# pico_tracker_v3_1.net
KiCad netlist of a schematic drawn in EAGLE
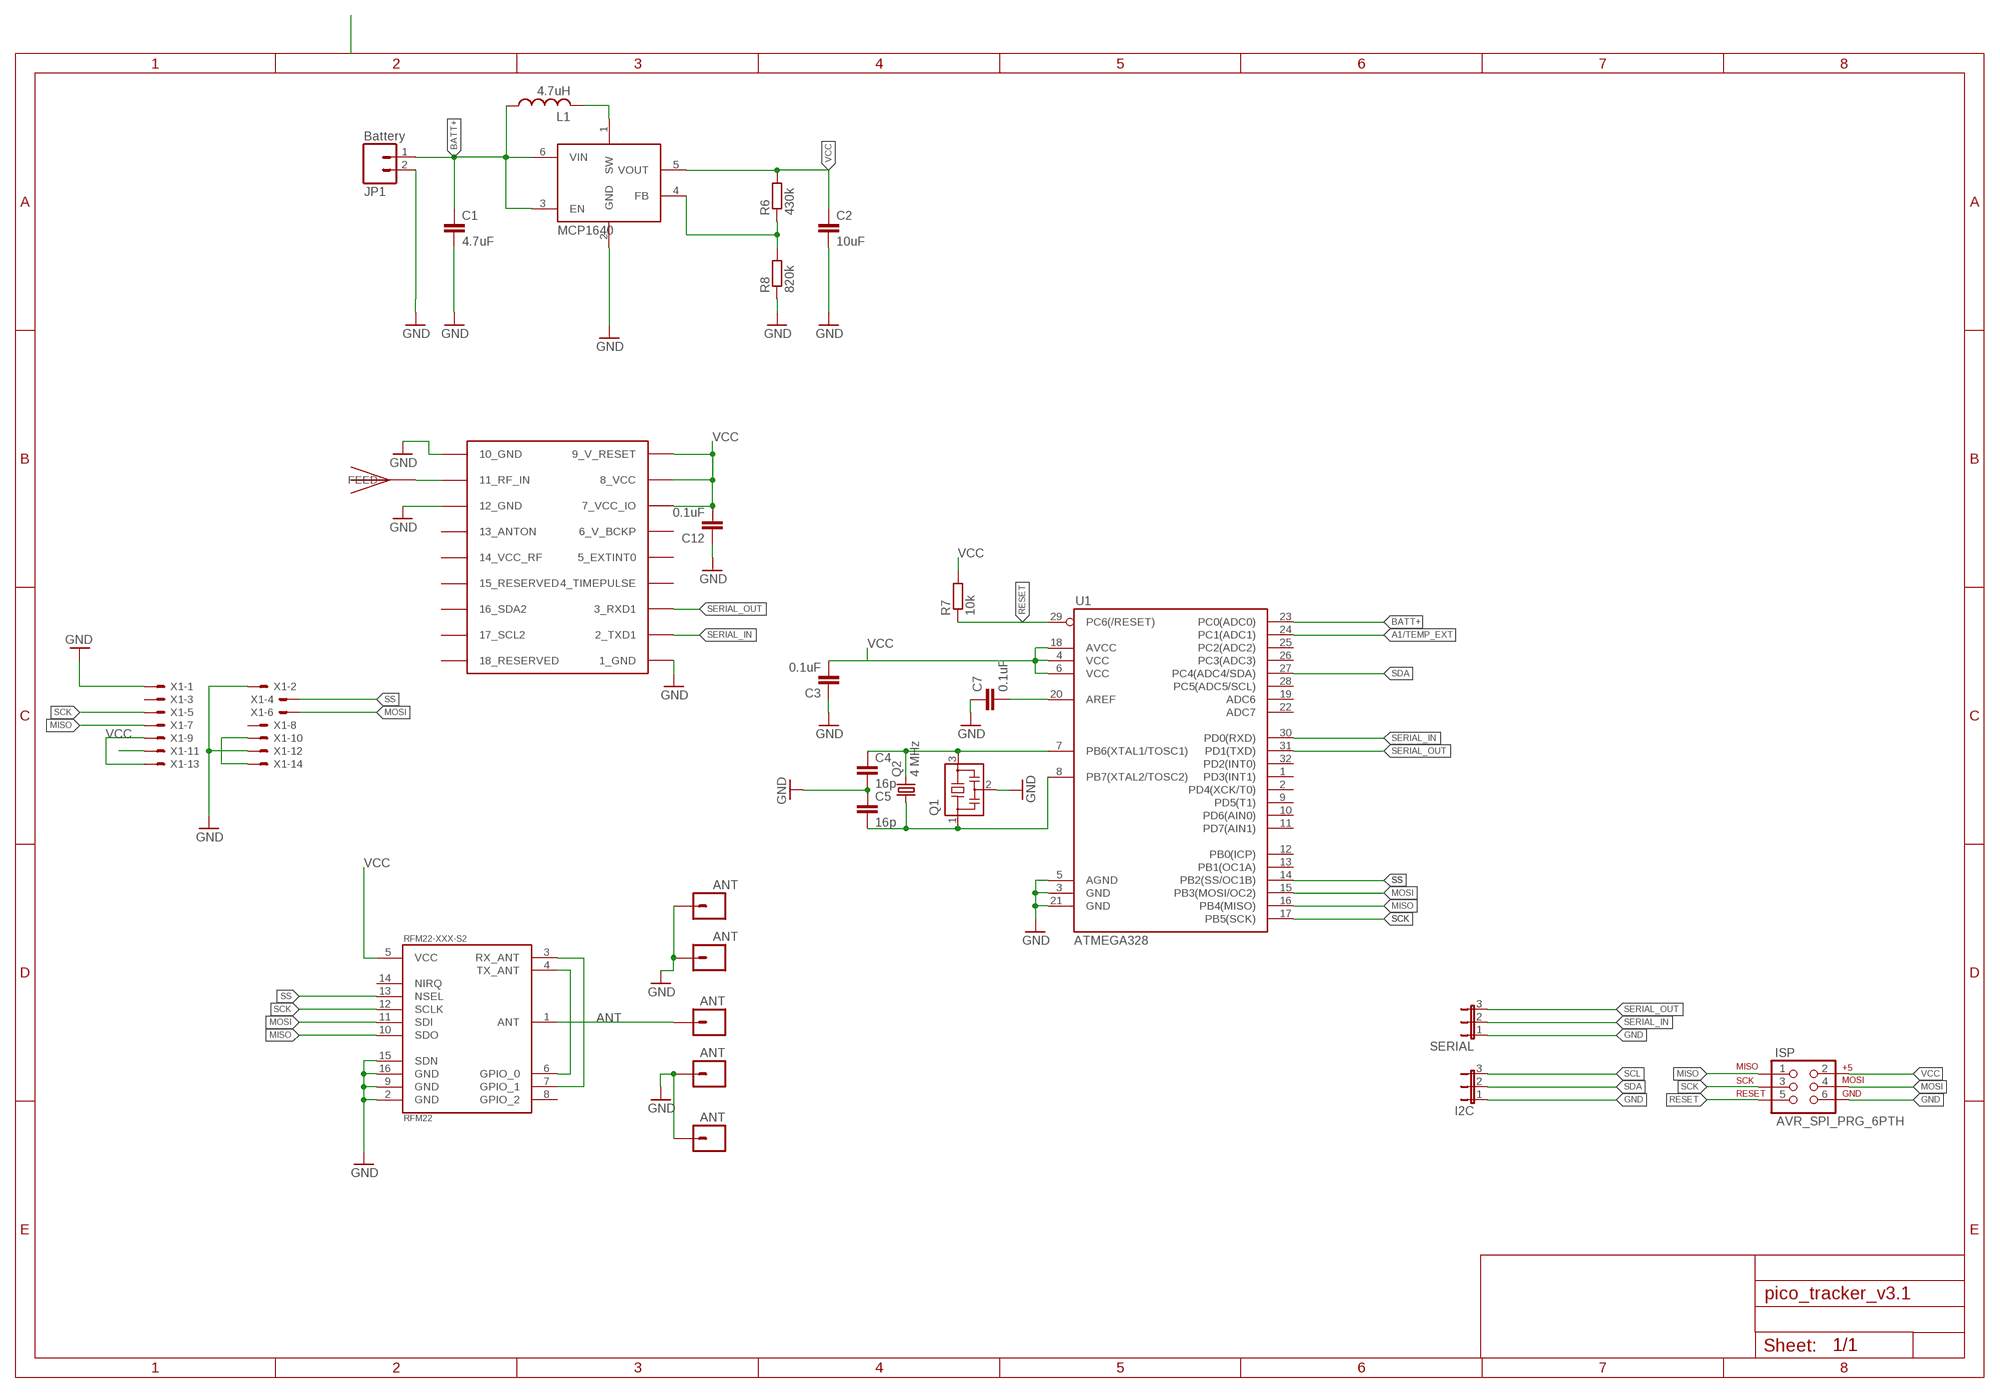
[diagram p0: schematic, sheet 1]

(export (version "E")
  (design (tool "Eeschema 10.0.6"))
  (components
    (comp (ref "C1")
      (value "4.7uF")
      (footprint "eagle-import:C0805")
      (libsource (lib "eagle-import") (part "C-EUC0805"))
    )
    (comp (ref "C2")
      (value "10uF")
      (footprint "eagle-import:C0805")
      (libsource (lib "eagle-import") (part "C-EUC0805"))
    )
    (comp (ref "C3")
      (value "0.1uF")
      (footprint "eagle-import:C0603")
      (libsource (lib "eagle-import") (part "C-EUC0603"))
    )
    (comp (ref "C4")
      (value "16p")
      (footprint "eagle-import:C0603")
      (libsource (lib "eagle-import") (part "C-EUC0603"))
    )
    (comp (ref "C5")
      (value "16p")
      (footprint "eagle-import:C0603")
      (libsource (lib "eagle-import") (part "C-EUC0603"))
    )
    (comp (ref "C7")
      (value "0.1uF")
      (footprint "eagle-import:C0603")
      (libsource (lib "eagle-import") (part "C-EUC0603"))
    )
    (comp (ref "C12")
      (value "0.1uF")
      (footprint "eagle-import:C0603")
      (libsource (lib "eagle-import") (part "C-EUC0603"))
    )
    (comp (ref "GND")
      (value "ANT")
      (footprint "eagle-import:1X01")
      (libsource (lib "eagle-import") (part "M01PTH"))
    )
    (comp (ref "GND17")
      (value "ANT")
      (footprint "eagle-import:1X01")
      (libsource (lib "eagle-import") (part "M01PTH"))
    )
    (comp (ref "GPS_ANT")
      (value "JTI_ANTENNA-1575AT43A40")
      (footprint "eagle-import:JTI_ANTENNA-1575AT43A40")
      (libsource (lib "eagle-import") (part "JTI_ANTENNA-1575AT43A40"))
    )
    (comp (ref "I2C")
      (value "JP2E")
      (footprint "eagle-import:JP2")
      (libsource (lib "eagle-import") (part "JP2E"))
    )
    (comp (ref "ISP")
      (value "AVR_SPI_PRG_6PTH")
      (footprint "eagle-import:2X3")
      (libsource (lib "eagle-import") (part "AVR_SPI_PRG_6PTH"))
    )
    (comp (ref "JP1")
      (value "Battery")
      (footprint "eagle-import:1X02")
      (libsource (lib "eagle-import") (part "M02PTH"))
    )
    (comp (ref "JP2")
      (value "ANT")
      (footprint "eagle-import:1X01")
      (libsource (lib "eagle-import") (part "M01PTH"))
    )
    (comp (ref "JP3")
      (value "ANT")
      (footprint "eagle-import:1X01")
      (libsource (lib "eagle-import") (part "M01PTH"))
    )
    (comp (ref "JP4")
      (value "ANT")
      (footprint "eagle-import:1X01")
      (libsource (lib "eagle-import") (part "M01PTH"))
    )
    (comp (ref "L1")
      (value "4.7uH")
      (footprint "eagle-import:LQH44")
      (libsource (lib "eagle-import") (part "LLQH44P_P0"))
    )
    (comp (ref "Q1")
      (value "CSTCR6M00G53Z")
      (footprint "eagle-import:CSTCR6M")
      (fields (field (name "MPN") "CSTCR6M00G53-R0"))
      (libsource (lib "eagle-import") (part "CSTCR6M00G53Z"))
    )
    (comp (ref "Q2")
      (value "4 MHz")
      (footprint "eagle-import:ABM03_HC49")
      (libsource (lib "eagle-import") (part "ABRACON_ABM3_CRYSTALABM03_HC49"))
    )
    (comp (ref "R6")
      (value "430k")
      (footprint "eagle-import:R0603")
      (libsource (lib "eagle-import") (part "R-EU_R0603"))
    )
    (comp (ref "R7")
      (value "10k")
      (footprint "eagle-import:R0603")
      (libsource (lib "eagle-import") (part "R-EU_R0603"))
    )
    (comp (ref "R8")
      (value "820k")
      (footprint "eagle-import:R0603")
      (libsource (lib "eagle-import") (part "R-EU_R0603"))
    )
    (comp (ref "RFM22-XXX-S2")
      (value "RFM22")
      (footprint "eagle-import:RFM22-XXX-S2")
      (libsource (lib "eagle-import") (part "RFM22"))
    )
    (comp (ref "SERIAL")
      (value "JP2E")
      (footprint "eagle-import:JP2")
      (libsource (lib "eagle-import") (part "JP2E"))
    )
    (comp (ref "U$3")
      (value "UBLOX_MAX-6")
      (footprint "eagle-import:UBLOX_MAX-6")
      (libsource (lib "eagle-import") (part "UBLOX_MAX-6"))
    )
    (comp (ref "U1")
      (value "ATMEGA328")
      (footprint "eagle-import:TQFP32-08")
      (libsource (lib "eagle-import") (part "ATMEGA168"))
    )
    (comp (ref "U2")
      (value "MCP1640")
      (footprint "eagle-import:SOT23-6")
      (libsource (lib "eagle-import") (part "MCP1640"))
    )
    (comp (ref "X1")
      (value "87758-1416")
      (footprint "eagle-import:87758-1416")
      (libsource (lib "eagle-import") (part "87758-1416"))
    )
  )
  (nets
    (net (code "1") (name "/ANT") (class "Default")
      (node (ref "JP2") (pin "1") (pinfunction "1_1") (pintype "passive"))
      (node (ref "RFM22-XXX-S2") (pin "1") (pinfunction "ANT_1") (pintype "bidirectional"))
    )
    (net (code "2") (name "A1{slash}TEMP_EXT") (class "Default")
      (node (ref "U1") (pin "24") (pinfunction "PC1(ADC1)_24") (pintype "bidirectional"))
    )
    (net (code "3") (name "BATT+") (class "Default")
      (node (ref "C1") (pin "1") (pinfunction "1_1") (pintype "passive"))
      (node (ref "JP1") (pin "1") (pinfunction "1_1") (pintype "passive"))
      (node (ref "L1") (pin "P$1") (pinfunction "1_P$1") (pintype "passive"))
      (node (ref "U1") (pin "23") (pinfunction "PC0(ADC0)_23") (pintype "bidirectional"))
      (node (ref "U2") (pin "3") (pinfunction "EN_3") (pintype "input"))
      (node (ref "U2") (pin "6") (pinfunction "VIN_6") (pintype "input"))
    )
    (net (code "4") (name "GND") (class "Default")
      (node (ref "C1") (pin "2") (pinfunction "2_2") (pintype "passive"))
      (node (ref "C12") (pin "1") (pinfunction "1_1") (pintype "passive"))
      (node (ref "C2") (pin "2") (pinfunction "2_2") (pintype "passive"))
      (node (ref "C3") (pin "1") (pinfunction "1_1") (pintype "passive"))
      (node (ref "C4") (pin "2") (pinfunction "2_2") (pintype "passive"))
      (node (ref "C5") (pin "1") (pinfunction "1_1") (pintype "passive"))
      (node (ref "C7") (pin "1") (pinfunction "1_1") (pintype "passive"))
      (node (ref "GND") (pin "1") (pinfunction "1_1") (pintype "passive"))
      (node (ref "GND17") (pin "1") (pinfunction "1_1") (pintype "passive"))
      (node (ref "I2C") (pin "1") (pinfunction "1_1") (pintype "passive"))
      (node (ref "ISP") (pin "6") (pinfunction "6_6") (pintype "passive"))
      (node (ref "JP1") (pin "2") (pinfunction "2_2") (pintype "passive"))
      (node (ref "JP3") (pin "1") (pinfunction "1_1") (pintype "passive"))
      (node (ref "JP4") (pin "1") (pinfunction "1_1") (pintype "passive"))
      (node (ref "Q1") (pin "2") (pinfunction "2_2") (pintype "passive"))
      (node (ref "R8") (pin "1") (pinfunction "1_1") (pintype "passive"))
      (node (ref "RFM22-XXX-S2") (pin "15") (pinfunction "SDN_15") (pintype "input"))
      (node (ref "RFM22-XXX-S2") (pin "16") (pinfunction "GND_16") (pintype "power_in"))
      (node (ref "RFM22-XXX-S2") (pin "2") (pinfunction "GND_2") (pintype "power_in"))
      (node (ref "RFM22-XXX-S2") (pin "9") (pinfunction "GND_9") (pintype "power_in"))
      (node (ref "SERIAL") (pin "1") (pinfunction "1_1") (pintype "passive"))
      (node (ref "U$3") (pin "10_GND") (pinfunction "10_GND_10_GND") (pintype "power_in"))
      (node (ref "U$3") (pin "12_GND") (pinfunction "12_GND_12_GND") (pintype "power_in"))
      (node (ref "U$3") (pin "1_GND") (pinfunction "1_GND_1_GND") (pintype "power_in"))
      (node (ref "U1") (pin "21") (pinfunction "GND_21") (pintype "bidirectional"))
      (node (ref "U1") (pin "3") (pinfunction "GND_3") (pintype "bidirectional"))
      (node (ref "U1") (pin "5") (pinfunction "AGND_5") (pintype "bidirectional"))
      (node (ref "U2") (pin "2") (pinfunction "GND_2") (pintype "power_in"))
      (node (ref "X1") (pin "1") (pinfunction "S_1") (pintype "passive"))
      (node (ref "X1") (pin "12") (pinfunction "S_12") (pintype "passive"))
      (node (ref "X1") (pin "2") (pinfunction "S_2") (pintype "passive"))
    )
    (net (code "5") (name "MISO") (class "Default")
      (node (ref "ISP") (pin "1") (pinfunction "1_1") (pintype "passive"))
      (node (ref "RFM22-XXX-S2") (pin "10") (pinfunction "SDO_10") (pintype "output"))
      (node (ref "U1") (pin "16") (pinfunction "PB4(MISO)_16") (pintype "bidirectional"))
      (node (ref "X1") (pin "7") (pinfunction "S_7") (pintype "passive"))
    )
    (net (code "6") (name "MOSI") (class "Default")
      (node (ref "ISP") (pin "4") (pinfunction "4_4") (pintype "passive"))
      (node (ref "RFM22-XXX-S2") (pin "11") (pinfunction "SDI_11") (pintype "input"))
      (node (ref "U1") (pin "15") (pinfunction "PB3(MOSI/OC2)_15") (pintype "bidirectional"))
      (node (ref "X1") (pin "6") (pinfunction "S_6") (pintype "passive"))
    )
    (net (code "7") (name "Net-(GPS_ANT-PadFEED)") (class "Default")
      (node (ref "GPS_ANT") (pin "FEED") (pinfunction "FEED_FEED") (pintype "bidirectional"))
      (node (ref "U$3") (pin "11_RF_IN") (pinfunction "11_RF_IN_11_RF_IN") (pintype "bidirectional"))
    )
    (net (code "8") (name "Net-(L1-2)") (class "Default")
      (node (ref "L1") (pin "P$2") (pinfunction "2_P$2") (pintype "passive"))
      (node (ref "U2") (pin "1") (pinfunction "SW_1") (pintype "output"))
    )
    (net (code "9") (name "Net-(RFM22-XXX-S2-GPIO_0)") (class "Default")
      (node (ref "RFM22-XXX-S2") (pin "4") (pinfunction "TX_ANT_4") (pintype "input"))
      (node (ref "RFM22-XXX-S2") (pin "6") (pinfunction "GPIO_0_6") (pintype "bidirectional"))
    )
    (net (code "10") (name "Net-(RFM22-XXX-S2-GPIO_1)") (class "Default")
      (node (ref "RFM22-XXX-S2") (pin "3") (pinfunction "RX_ANT_3") (pintype "input"))
      (node (ref "RFM22-XXX-S2") (pin "7") (pinfunction "GPIO_1_7") (pintype "bidirectional"))
    )
    (net (code "11") (name "Net-(U1-AREF)") (class "Default")
      (node (ref "C7") (pin "2") (pinfunction "2_2") (pintype "passive"))
      (node (ref "U1") (pin "20") (pinfunction "AREF_20") (pintype "bidirectional"))
    )
    (net (code "12") (name "Net-(U1-PB6(XTAL1{slash}TOSC1))") (class "Default")
      (node (ref "C4") (pin "1") (pinfunction "1_1") (pintype "passive"))
      (node (ref "Q1") (pin "3") (pinfunction "3_3") (pintype "passive"))
      (node (ref "Q2") (pin "2") (pinfunction "2_2") (pintype "passive"))
      (node (ref "U1") (pin "7") (pinfunction "PB6(XTAL1/TOSC1)_7") (pintype "bidirectional"))
    )
    (net (code "13") (name "Net-(U1-PB7(XTAL2{slash}TOSC2))") (class "Default")
      (node (ref "C5") (pin "2") (pinfunction "2_2") (pintype "passive"))
      (node (ref "Q1") (pin "1") (pinfunction "1_1") (pintype "passive"))
      (node (ref "Q2") (pin "1") (pinfunction "1_1") (pintype "passive"))
      (node (ref "U1") (pin "8") (pinfunction "PB7(XTAL2/TOSC2)_8") (pintype "bidirectional"))
    )
    (net (code "14") (name "Net-(U2-FB)") (class "Default")
      (node (ref "R6") (pin "1") (pinfunction "1_1") (pintype "passive"))
      (node (ref "R8") (pin "2") (pinfunction "2_2") (pintype "passive"))
      (node (ref "U2") (pin "4") (pinfunction "FB_4") (pintype "input"))
    )
    (net (code "15") (name "Net-(X1B-S)") (class "Default")
      (node (ref "X1") (pin "10") (pinfunction "S_10") (pintype "passive"))
      (node (ref "X1") (pin "14") (pinfunction "S_14") (pintype "passive"))
    )
    (net (code "16") (name "Net-(X1E-S)") (class "Default")
      (node (ref "X1") (pin "13") (pinfunction "S_13") (pintype "passive"))
      (node (ref "X1") (pin "9") (pinfunction "S_9") (pintype "passive"))
    )
    (net (code "17") (name "RESET") (class "Default")
      (node (ref "ISP") (pin "5") (pinfunction "5_5") (pintype "passive"))
      (node (ref "R7") (pin "1") (pinfunction "1_1") (pintype "passive"))
      (node (ref "U1") (pin "29") (pinfunction "PC6(/RESET)_29") (pintype "bidirectional"))
    )
    (net (code "18") (name "SCK") (class "Default")
      (node (ref "ISP") (pin "3") (pinfunction "3_3") (pintype "passive"))
      (node (ref "RFM22-XXX-S2") (pin "12") (pinfunction "SCLK_12") (pintype "input"))
      (node (ref "U1") (pin "17") (pinfunction "PB5(SCK)_17") (pintype "bidirectional"))
      (node (ref "X1") (pin "5") (pinfunction "S_5") (pintype "passive"))
    )
    (net (code "19") (name "SCL") (class "Default")
      (node (ref "I2C") (pin "3") (pinfunction "3_3") (pintype "passive"))
    )
    (net (code "20") (name "SDA") (class "Default")
      (node (ref "I2C") (pin "2") (pinfunction "2_2") (pintype "passive"))
      (node (ref "U1") (pin "27") (pinfunction "PC4(ADC4/SDA)_27") (pintype "bidirectional"))
    )
    (net (code "21") (name "SERIAL_IN") (class "Default")
      (node (ref "SERIAL") (pin "2") (pinfunction "2_2") (pintype "passive"))
      (node (ref "U$3") (pin "2_TXD1") (pinfunction "2_TXD1_2_TXD1") (pintype "bidirectional"))
      (node (ref "U1") (pin "30") (pinfunction "PD0(RXD)_30") (pintype "bidirectional"))
    )
    (net (code "22") (name "SERIAL_OUT") (class "Default")
      (node (ref "SERIAL") (pin "3") (pinfunction "3_3") (pintype "passive"))
      (node (ref "U$3") (pin "3_RXD1") (pinfunction "3_RXD1_3_RXD1") (pintype "bidirectional"))
      (node (ref "U1") (pin "31") (pinfunction "PD1(TXD)_31") (pintype "bidirectional"))
    )
    (net (code "23") (name "SS") (class "Default")
      (node (ref "RFM22-XXX-S2") (pin "13") (pinfunction "NSEL_13") (pintype "input"))
      (node (ref "U1") (pin "14") (pinfunction "PB2(SS/OC1B)_14") (pintype "bidirectional"))
      (node (ref "X1") (pin "4") (pinfunction "S_4") (pintype "passive"))
    )
    (net (code "24") (name "VCC") (class "Default")
      (node (ref "C12") (pin "2") (pinfunction "2_2") (pintype "passive"))
      (node (ref "C2") (pin "1") (pinfunction "1_1") (pintype "passive"))
      (node (ref "C3") (pin "2") (pinfunction "2_2") (pintype "passive"))
      (node (ref "ISP") (pin "2") (pinfunction "2_2") (pintype "passive"))
      (node (ref "R6") (pin "2") (pinfunction "2_2") (pintype "passive"))
      (node (ref "R7") (pin "2") (pinfunction "2_2") (pintype "passive"))
      (node (ref "RFM22-XXX-S2") (pin "5") (pinfunction "VCC_5") (pintype "bidirectional"))
      (node (ref "U$3") (pin "7_VCC_IO") (pinfunction "7_VCC_IO_7_VCC_IO") (pintype "power_in"))
      (node (ref "U$3") (pin "8_VCC") (pinfunction "8_VCC_8_VCC") (pintype "power_in"))
      (node (ref "U$3") (pin "9_V_RESET") (pinfunction "9_V_RESET_9_V_RESET") (pintype "power_in"))
      (node (ref "U1") (pin "18") (pinfunction "AVCC_18") (pintype "bidirectional"))
      (node (ref "U1") (pin "4") (pinfunction "VCC_4") (pintype "bidirectional"))
      (node (ref "U1") (pin "6") (pinfunction "VCC_6") (pintype "bidirectional"))
      (node (ref "U2") (pin "5") (pinfunction "VOUT_5") (pintype "output"))
      (node (ref "X1") (pin "11") (pinfunction "S_11") (pintype "passive"))
    )
    (net (code "25") (name "unconnected-(RFM22-XXX-S2-GPIO_2-Pad8)") (class "Default")
      (node (ref "RFM22-XXX-S2") (pin "8") (pinfunction "GPIO_2_8") (pintype "bidirectional"))
    )
    (net (code "26") (name "unconnected-(RFM22-XXX-S2-NIRQ-Pad14)") (class "Default")
      (node (ref "RFM22-XXX-S2") (pin "14") (pinfunction "NIRQ_14") (pintype "output"))
    )
    (net (code "27") (name "unconnected-(U$3-Pad4_TIMEPULSE)") (class "Default")
      (node (ref "U$3") (pin "4_TIMEPULSE") (pinfunction "4_TIMEPULSE_4_TIMEPULSE") (pintype "bidirectional"))
    )
    (net (code "28") (name "unconnected-(U$3-Pad5_EXTINT0)") (class "Default")
      (node (ref "U$3") (pin "5_EXTINT0") (pinfunction "5_EXTINT0_5_EXTINT0") (pintype "bidirectional"))
    )
    (net (code "29") (name "unconnected-(U$3-Pad6_V_BCKP)") (class "Default")
      (node (ref "U$3") (pin "6_V_BCKP") (pinfunction "6_V_BCKP_6_V_BCKP") (pintype "bidirectional"))
    )
    (net (code "30") (name "unconnected-(U$3-Pad13_ANTON)") (class "Default")
      (node (ref "U$3") (pin "13_ANTON") (pinfunction "13_ANTON_13_ANTON") (pintype "bidirectional"))
    )
    (net (code "31") (name "unconnected-(U$3-Pad14_VCC_RF)") (class "Default")
      (node (ref "U$3") (pin "14_VCC_RF") (pinfunction "14_VCC_RF_14_VCC_RF") (pintype "bidirectional"))
    )
    (net (code "32") (name "unconnected-(U$3-Pad15_RESERVED)") (class "Default")
      (node (ref "U$3") (pin "15_RESERVED") (pinfunction "15_RESERVED_15_RESERVED") (pintype "bidirectional"))
    )
    (net (code "33") (name "unconnected-(U$3-Pad16_SDA2)") (class "Default")
      (node (ref "U$3") (pin "16_SDA2") (pinfunction "16_SDA2_16_SDA2") (pintype "bidirectional"))
    )
    (net (code "34") (name "unconnected-(U$3-Pad17_SCL2)") (class "Default")
      (node (ref "U$3") (pin "17_SCL2") (pinfunction "17_SCL2_17_SCL2") (pintype "bidirectional"))
    )
    (net (code "35") (name "unconnected-(U$3-Pad18_RESERVED)") (class "Default")
      (node (ref "U$3") (pin "18_RESERVED") (pinfunction "18_RESERVED_18_RESERVED") (pintype "bidirectional"))
    )
    (net (code "36") (name "unconnected-(U1-ADC6-Pad19)") (class "Default")
      (node (ref "U1") (pin "19") (pinfunction "ADC6_19") (pintype "bidirectional"))
    )
    (net (code "37") (name "unconnected-(U1-ADC7-Pad22)") (class "Default")
      (node (ref "U1") (pin "22") (pinfunction "ADC7_22") (pintype "bidirectional"))
    )
    (net (code "38") (name "unconnected-(U1-PB0(ICP)-Pad12)") (class "Default")
      (node (ref "U1") (pin "12") (pinfunction "PB0(ICP)_12") (pintype "bidirectional"))
    )
    (net (code "39") (name "unconnected-(U1-PB1(OC1A)-Pad13)") (class "Default")
      (node (ref "U1") (pin "13") (pinfunction "PB1(OC1A)_13") (pintype "bidirectional"))
    )
    (net (code "40") (name "unconnected-(U1-PC2(ADC2)-Pad25)") (class "Default")
      (node (ref "U1") (pin "25") (pinfunction "PC2(ADC2)_25") (pintype "bidirectional"))
    )
    (net (code "41") (name "unconnected-(U1-PC3(ADC3)-Pad26)") (class "Default")
      (node (ref "U1") (pin "26") (pinfunction "PC3(ADC3)_26") (pintype "bidirectional"))
    )
    (net (code "42") (name "unconnected-(U1-PC5(ADC5{slash}SCL)-Pad28)") (class "Default")
      (node (ref "U1") (pin "28") (pinfunction "PC5(ADC5/SCL)_28") (pintype "bidirectional"))
    )
    (net (code "43") (name "unconnected-(U1-PD2(INT0)-Pad32)") (class "Default")
      (node (ref "U1") (pin "32") (pinfunction "PD2(INT0)_32") (pintype "bidirectional"))
    )
    (net (code "44") (name "unconnected-(U1-PD3(INT1)-Pad1)") (class "Default")
      (node (ref "U1") (pin "1") (pinfunction "PD3(INT1)_1") (pintype "bidirectional"))
    )
    (net (code "45") (name "unconnected-(U1-PD4(XCK{slash}T0)-Pad2)") (class "Default")
      (node (ref "U1") (pin "2") (pinfunction "PD4(XCK/T0)_2") (pintype "bidirectional"))
    )
    (net (code "46") (name "unconnected-(U1-PD5(T1)-Pad9)") (class "Default")
      (node (ref "U1") (pin "9") (pinfunction "PD5(T1)_9") (pintype "bidirectional"))
    )
    (net (code "47") (name "unconnected-(U1-PD6(AIN0)-Pad10)") (class "Default")
      (node (ref "U1") (pin "10") (pinfunction "PD6(AIN0)_10") (pintype "bidirectional"))
    )
    (net (code "48") (name "unconnected-(U1-PD7(AIN1)-Pad11)") (class "Default")
      (node (ref "U1") (pin "11") (pinfunction "PD7(AIN1)_11") (pintype "bidirectional"))
    )
    (net (code "49") (name "unconnected-(X1H-S-Pad3)") (class "Default")
      (node (ref "X1") (pin "3") (pinfunction "S_3") (pintype "passive"))
    )
    (net (code "50") (name "unconnected-(X1M-S-Pad8)") (class "Default")
      (node (ref "X1") (pin "8") (pinfunction "S_8") (pintype "passive"))
    )
  )
)
